# valve_driver.net
KiCad netlist of a schematic drawn in EAGLE
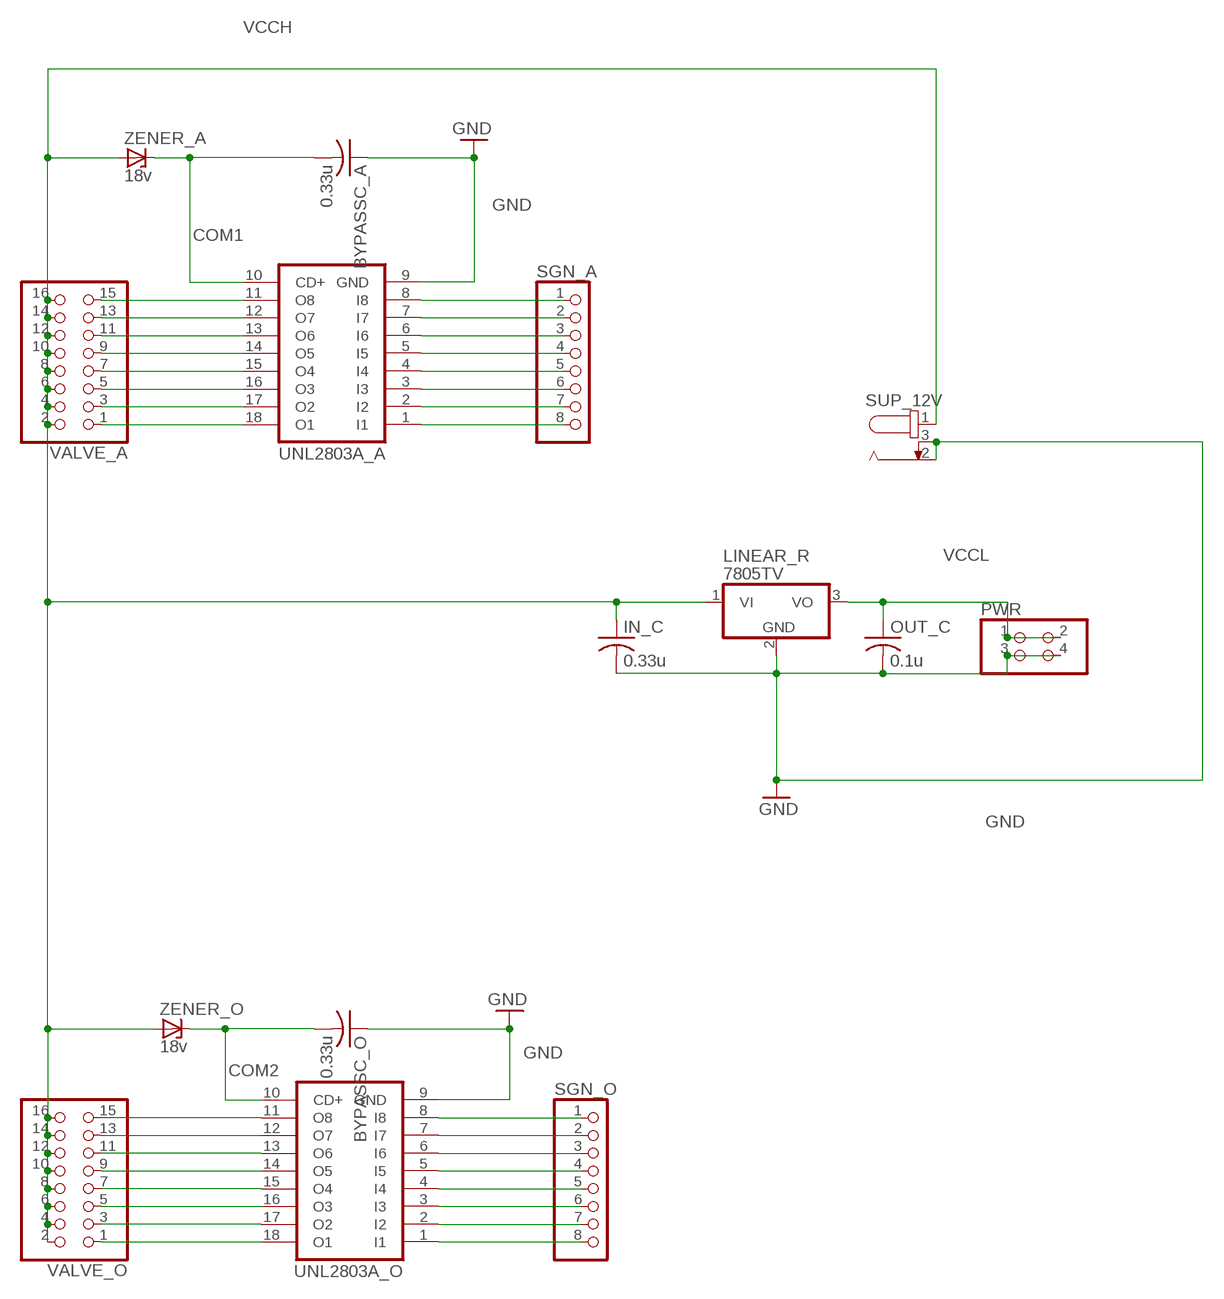
[diagram p0: schematic, sheet 1]

(export (version "E")
  (design (tool "Eeschema 10.0.6"))
  (components
    (comp (ref "BYPASSC_A")
      (value "0.33u")
      (footprint "eagle-import:C050-024X044")
      (libsource (lib "eagle-import") (part "resistor_348_C-US050-024X044"))
    )
    (comp (ref "BYPASSC_O")
      (value "0.33u")
      (footprint "eagle-import:C050-024X044")
      (libsource (lib "eagle-import") (part "resistor_348_C-US050-024X044"))
    )
    (comp (ref "IN_C")
      (value "0.33u")
      (footprint "eagle-import:C050-024X044")
      (libsource (lib "eagle-import") (part "C-US050-024X044"))
    )
    (comp (ref "LINEAR_R")
      (value "7805TV")
      (footprint "eagle-import:TO220V")
      (libsource (lib "eagle-import") (part "78TV05"))
    )
    (comp (ref "OUT_C")
      (value "0.1u")
      (footprint "eagle-import:C050-024X044")
      (libsource (lib "eagle-import") (part "C-US050-024X044"))
    )
    (comp (ref "PWR")
      (value "PINHD-2X2")
      (footprint "eagle-import:2X02")
      (libsource (lib "eagle-import") (part "PINHD-2X2"))
    )
    (comp (ref "SGN_A")
      (value "PINHD-1X8")
      (footprint "eagle-import:1X08")
      (libsource (lib "eagle-import") (part "PINHD-1X8"))
    )
    (comp (ref "SGN_O")
      (value "PINHD-1X8")
      (footprint "eagle-import:1X08")
      (libsource (lib "eagle-import") (part "PINHD-1X8"))
    )
    (comp (ref "SUP_12V")
      (value "694108301002")
      (footprint "eagle-import:69410X301002")
      (libsource (lib "eagle-import") (part "694108301002"))
    )
    (comp (ref "UNL2803A_A")
      (value "ULN2803A")
      (footprint "eagle-import:DIL18")
      (libsource (lib "eagle-import") (part "ULN2803A"))
    )
    (comp (ref "UNL2803A_O")
      (value "ULN2803A")
      (footprint "eagle-import:DIL18")
      (libsource (lib "eagle-import") (part "ULN2803A"))
    )
    (comp (ref "VALVE_A")
      (value "PINHD-2X8")
      (footprint "eagle-import:2X08")
      (libsource (lib "eagle-import") (part "PINHD-2X8"))
    )
    (comp (ref "VALVE_O")
      (value "PINHD-2X8")
      (footprint "eagle-import:2X08")
      (libsource (lib "eagle-import") (part "PINHD-2X8"))
    )
    (comp (ref "ZENER_A")
      (value "18v")
      (footprint "eagle-import:DO35Z10")
      (libsource (lib "eagle-import") (part "1N821"))
    )
    (comp (ref "ZENER_O")
      (value "18v")
      (footprint "eagle-import:DO35Z10")
      (libsource (lib "eagle-import") (part "1N821"))
    )
  )
  (nets
    (net (code "1") (name "/COM1") (class "Default")
      (node (ref "BYPASSC_A") (pin "2") (pinfunction "2_2") (pintype "passive"))
      (node (ref "UNL2803A_A") (pin "10") (pinfunction "CD+_10") (pintype "passive"))
      (node (ref "ZENER_A") (pin "C") (pinfunction "C_C") (pintype "passive"))
    )
    (net (code "2") (name "/COM2") (class "Default")
      (node (ref "BYPASSC_O") (pin "2") (pinfunction "2_2") (pintype "passive"))
      (node (ref "UNL2803A_O") (pin "10") (pinfunction "CD+_10") (pintype "passive"))
      (node (ref "ZENER_O") (pin "C") (pinfunction "C_C") (pintype "passive"))
    )
    (net (code "3") (name "/VCCH") (class "Default")
      (node (ref "IN_C") (pin "1") (pinfunction "1_1") (pintype "passive"))
      (node (ref "LINEAR_R") (pin "1") (pinfunction "VI_1") (pintype "input"))
      (node (ref "SUP_12V") (pin "1") (pinfunction "1_1") (pintype "passive"))
      (node (ref "VALVE_A") (pin "10") (pinfunction "10_10") (pintype "passive"))
      (node (ref "VALVE_A") (pin "12") (pinfunction "12_12") (pintype "passive"))
      (node (ref "VALVE_A") (pin "14") (pinfunction "14_14") (pintype "passive"))
      (node (ref "VALVE_A") (pin "16") (pinfunction "16_16") (pintype "passive"))
      (node (ref "VALVE_A") (pin "2") (pinfunction "2_2") (pintype "passive"))
      (node (ref "VALVE_A") (pin "4") (pinfunction "4_4") (pintype "passive"))
      (node (ref "VALVE_A") (pin "6") (pinfunction "6_6") (pintype "passive"))
      (node (ref "VALVE_A") (pin "8") (pinfunction "8_8") (pintype "passive"))
      (node (ref "VALVE_O") (pin "10") (pinfunction "10_10") (pintype "passive"))
      (node (ref "VALVE_O") (pin "12") (pinfunction "12_12") (pintype "passive"))
      (node (ref "VALVE_O") (pin "14") (pinfunction "14_14") (pintype "passive"))
      (node (ref "VALVE_O") (pin "16") (pinfunction "16_16") (pintype "passive"))
      (node (ref "VALVE_O") (pin "2") (pinfunction "2_2") (pintype "passive"))
      (node (ref "VALVE_O") (pin "4") (pinfunction "4_4") (pintype "passive"))
      (node (ref "VALVE_O") (pin "6") (pinfunction "6_6") (pintype "passive"))
      (node (ref "VALVE_O") (pin "8") (pinfunction "8_8") (pintype "passive"))
      (node (ref "ZENER_A") (pin "A") (pinfunction "A_A") (pintype "passive"))
      (node (ref "ZENER_O") (pin "A") (pinfunction "A_A") (pintype "passive"))
    )
    (net (code "4") (name "/VCCL") (class "Default")
      (node (ref "LINEAR_R") (pin "3") (pinfunction "VO_3") (pintype "passive"))
      (node (ref "OUT_C") (pin "1") (pinfunction "1_1") (pintype "passive"))
      (node (ref "PWR") (pin "1") (pinfunction "1_1") (pintype "passive"))
      (node (ref "PWR") (pin "2") (pinfunction "2_2") (pintype "passive"))
    )
    (net (code "5") (name "GND") (class "Default")
      (node (ref "BYPASSC_A") (pin "1") (pinfunction "1_1") (pintype "passive"))
      (node (ref "BYPASSC_O") (pin "1") (pinfunction "1_1") (pintype "passive"))
      (node (ref "IN_C") (pin "2") (pinfunction "2_2") (pintype "passive"))
      (node (ref "LINEAR_R") (pin "2") (pinfunction "GND_2") (pintype "passive"))
      (node (ref "OUT_C") (pin "2") (pinfunction "2_2") (pintype "passive"))
      (node (ref "PWR") (pin "3") (pinfunction "3_3") (pintype "passive"))
      (node (ref "PWR") (pin "4") (pinfunction "4_4") (pintype "passive"))
      (node (ref "SUP_12V") (pin "2") (pinfunction "2_2") (pintype "passive"))
      (node (ref "SUP_12V") (pin "3") (pinfunction "3_3") (pintype "passive"))
      (node (ref "UNL2803A_A") (pin "9") (pinfunction "GND_9") (pintype "power_in"))
      (node (ref "UNL2803A_O") (pin "9") (pinfunction "GND_9") (pintype "power_in"))
    )
    (net (code "6") (name "Net-(UNL2803A_A-I1)") (class "Default")
      (node (ref "SGN_A") (pin "8") (pinfunction "8_8") (pintype "passive"))
      (node (ref "UNL2803A_A") (pin "1") (pinfunction "I1_1") (pintype "input"))
    )
    (net (code "7") (name "Net-(UNL2803A_A-I2)") (class "Default")
      (node (ref "SGN_A") (pin "7") (pinfunction "7_7") (pintype "passive"))
      (node (ref "UNL2803A_A") (pin "2") (pinfunction "I2_2") (pintype "input"))
    )
    (net (code "8") (name "Net-(UNL2803A_A-I3)") (class "Default")
      (node (ref "SGN_A") (pin "6") (pinfunction "6_6") (pintype "passive"))
      (node (ref "UNL2803A_A") (pin "3") (pinfunction "I3_3") (pintype "input"))
    )
    (net (code "9") (name "Net-(UNL2803A_A-I4)") (class "Default")
      (node (ref "SGN_A") (pin "5") (pinfunction "5_5") (pintype "passive"))
      (node (ref "UNL2803A_A") (pin "4") (pinfunction "I4_4") (pintype "input"))
    )
    (net (code "10") (name "Net-(UNL2803A_A-I5)") (class "Default")
      (node (ref "SGN_A") (pin "4") (pinfunction "4_4") (pintype "passive"))
      (node (ref "UNL2803A_A") (pin "5") (pinfunction "I5_5") (pintype "input"))
    )
    (net (code "11") (name "Net-(UNL2803A_A-I6)") (class "Default")
      (node (ref "SGN_A") (pin "3") (pinfunction "3_3") (pintype "passive"))
      (node (ref "UNL2803A_A") (pin "6") (pinfunction "I6_6") (pintype "input"))
    )
    (net (code "12") (name "Net-(UNL2803A_A-I7)") (class "Default")
      (node (ref "SGN_A") (pin "2") (pinfunction "2_2") (pintype "passive"))
      (node (ref "UNL2803A_A") (pin "7") (pinfunction "I7_7") (pintype "input"))
    )
    (net (code "13") (name "Net-(UNL2803A_A-I8)") (class "Default")
      (node (ref "SGN_A") (pin "1") (pinfunction "1_1") (pintype "passive"))
      (node (ref "UNL2803A_A") (pin "8") (pinfunction "I8_8") (pintype "input"))
    )
    (net (code "14") (name "Net-(UNL2803A_A-O1)") (class "Default")
      (node (ref "UNL2803A_A") (pin "18") (pinfunction "O1_18") (pintype "open_collector"))
      (node (ref "VALVE_A") (pin "1") (pinfunction "1_1") (pintype "passive"))
    )
    (net (code "15") (name "Net-(UNL2803A_A-O2)") (class "Default")
      (node (ref "UNL2803A_A") (pin "17") (pinfunction "O2_17") (pintype "open_collector"))
      (node (ref "VALVE_A") (pin "3") (pinfunction "3_3") (pintype "passive"))
    )
    (net (code "16") (name "Net-(UNL2803A_A-O3)") (class "Default")
      (node (ref "UNL2803A_A") (pin "16") (pinfunction "O3_16") (pintype "open_collector"))
      (node (ref "VALVE_A") (pin "5") (pinfunction "5_5") (pintype "passive"))
    )
    (net (code "17") (name "Net-(UNL2803A_A-O4)") (class "Default")
      (node (ref "UNL2803A_A") (pin "15") (pinfunction "O4_15") (pintype "open_collector"))
      (node (ref "VALVE_A") (pin "7") (pinfunction "7_7") (pintype "passive"))
    )
    (net (code "18") (name "Net-(UNL2803A_A-O5)") (class "Default")
      (node (ref "UNL2803A_A") (pin "14") (pinfunction "O5_14") (pintype "open_collector"))
      (node (ref "VALVE_A") (pin "9") (pinfunction "9_9") (pintype "passive"))
    )
    (net (code "19") (name "Net-(UNL2803A_A-O6)") (class "Default")
      (node (ref "UNL2803A_A") (pin "13") (pinfunction "O6_13") (pintype "open_collector"))
      (node (ref "VALVE_A") (pin "11") (pinfunction "11_11") (pintype "passive"))
    )
    (net (code "20") (name "Net-(UNL2803A_A-O7)") (class "Default")
      (node (ref "UNL2803A_A") (pin "12") (pinfunction "O7_12") (pintype "open_collector"))
      (node (ref "VALVE_A") (pin "13") (pinfunction "13_13") (pintype "passive"))
    )
    (net (code "21") (name "Net-(UNL2803A_A-O8)") (class "Default")
      (node (ref "UNL2803A_A") (pin "11") (pinfunction "O8_11") (pintype "open_collector"))
      (node (ref "VALVE_A") (pin "15") (pinfunction "15_15") (pintype "passive"))
    )
    (net (code "22") (name "Net-(UNL2803A_O-I1)") (class "Default")
      (node (ref "SGN_O") (pin "8") (pinfunction "8_8") (pintype "passive"))
      (node (ref "UNL2803A_O") (pin "1") (pinfunction "I1_1") (pintype "input"))
    )
    (net (code "23") (name "Net-(UNL2803A_O-I2)") (class "Default")
      (node (ref "SGN_O") (pin "7") (pinfunction "7_7") (pintype "passive"))
      (node (ref "UNL2803A_O") (pin "2") (pinfunction "I2_2") (pintype "input"))
    )
    (net (code "24") (name "Net-(UNL2803A_O-I3)") (class "Default")
      (node (ref "SGN_O") (pin "6") (pinfunction "6_6") (pintype "passive"))
      (node (ref "UNL2803A_O") (pin "3") (pinfunction "I3_3") (pintype "input"))
    )
    (net (code "25") (name "Net-(UNL2803A_O-I4)") (class "Default")
      (node (ref "SGN_O") (pin "5") (pinfunction "5_5") (pintype "passive"))
      (node (ref "UNL2803A_O") (pin "4") (pinfunction "I4_4") (pintype "input"))
    )
    (net (code "26") (name "Net-(UNL2803A_O-I5)") (class "Default")
      (node (ref "SGN_O") (pin "4") (pinfunction "4_4") (pintype "passive"))
      (node (ref "UNL2803A_O") (pin "5") (pinfunction "I5_5") (pintype "input"))
    )
    (net (code "27") (name "Net-(UNL2803A_O-I6)") (class "Default")
      (node (ref "SGN_O") (pin "3") (pinfunction "3_3") (pintype "passive"))
      (node (ref "UNL2803A_O") (pin "6") (pinfunction "I6_6") (pintype "input"))
    )
    (net (code "28") (name "Net-(UNL2803A_O-I7)") (class "Default")
      (node (ref "SGN_O") (pin "2") (pinfunction "2_2") (pintype "passive"))
      (node (ref "UNL2803A_O") (pin "7") (pinfunction "I7_7") (pintype "input"))
    )
    (net (code "29") (name "Net-(UNL2803A_O-I8)") (class "Default")
      (node (ref "SGN_O") (pin "1") (pinfunction "1_1") (pintype "passive"))
      (node (ref "UNL2803A_O") (pin "8") (pinfunction "I8_8") (pintype "input"))
    )
    (net (code "30") (name "Net-(UNL2803A_O-O1)") (class "Default")
      (node (ref "UNL2803A_O") (pin "18") (pinfunction "O1_18") (pintype "open_collector"))
      (node (ref "VALVE_O") (pin "1") (pinfunction "1_1") (pintype "passive"))
    )
    (net (code "31") (name "Net-(UNL2803A_O-O2)") (class "Default")
      (node (ref "UNL2803A_O") (pin "17") (pinfunction "O2_17") (pintype "open_collector"))
      (node (ref "VALVE_O") (pin "3") (pinfunction "3_3") (pintype "passive"))
    )
    (net (code "32") (name "Net-(UNL2803A_O-O3)") (class "Default")
      (node (ref "UNL2803A_O") (pin "16") (pinfunction "O3_16") (pintype "open_collector"))
      (node (ref "VALVE_O") (pin "5") (pinfunction "5_5") (pintype "passive"))
    )
    (net (code "33") (name "Net-(UNL2803A_O-O4)") (class "Default")
      (node (ref "UNL2803A_O") (pin "15") (pinfunction "O4_15") (pintype "open_collector"))
      (node (ref "VALVE_O") (pin "7") (pinfunction "7_7") (pintype "passive"))
    )
    (net (code "34") (name "Net-(UNL2803A_O-O5)") (class "Default")
      (node (ref "UNL2803A_O") (pin "14") (pinfunction "O5_14") (pintype "open_collector"))
      (node (ref "VALVE_O") (pin "9") (pinfunction "9_9") (pintype "passive"))
    )
    (net (code "35") (name "Net-(UNL2803A_O-O6)") (class "Default")
      (node (ref "UNL2803A_O") (pin "13") (pinfunction "O6_13") (pintype "open_collector"))
      (node (ref "VALVE_O") (pin "11") (pinfunction "11_11") (pintype "passive"))
    )
    (net (code "36") (name "Net-(UNL2803A_O-O7)") (class "Default")
      (node (ref "UNL2803A_O") (pin "12") (pinfunction "O7_12") (pintype "open_collector"))
      (node (ref "VALVE_O") (pin "13") (pinfunction "13_13") (pintype "passive"))
    )
    (net (code "37") (name "Net-(UNL2803A_O-O8)") (class "Default")
      (node (ref "UNL2803A_O") (pin "11") (pinfunction "O8_11") (pintype "open_collector"))
      (node (ref "VALVE_O") (pin "15") (pinfunction "15_15") (pintype "passive"))
    )
  )
)
